# 1.net
KiCad netlist of a schematic drawn in EAGLE
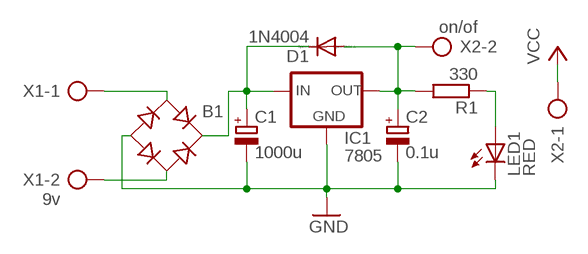
[diagram p0: schematic, sheet 1]
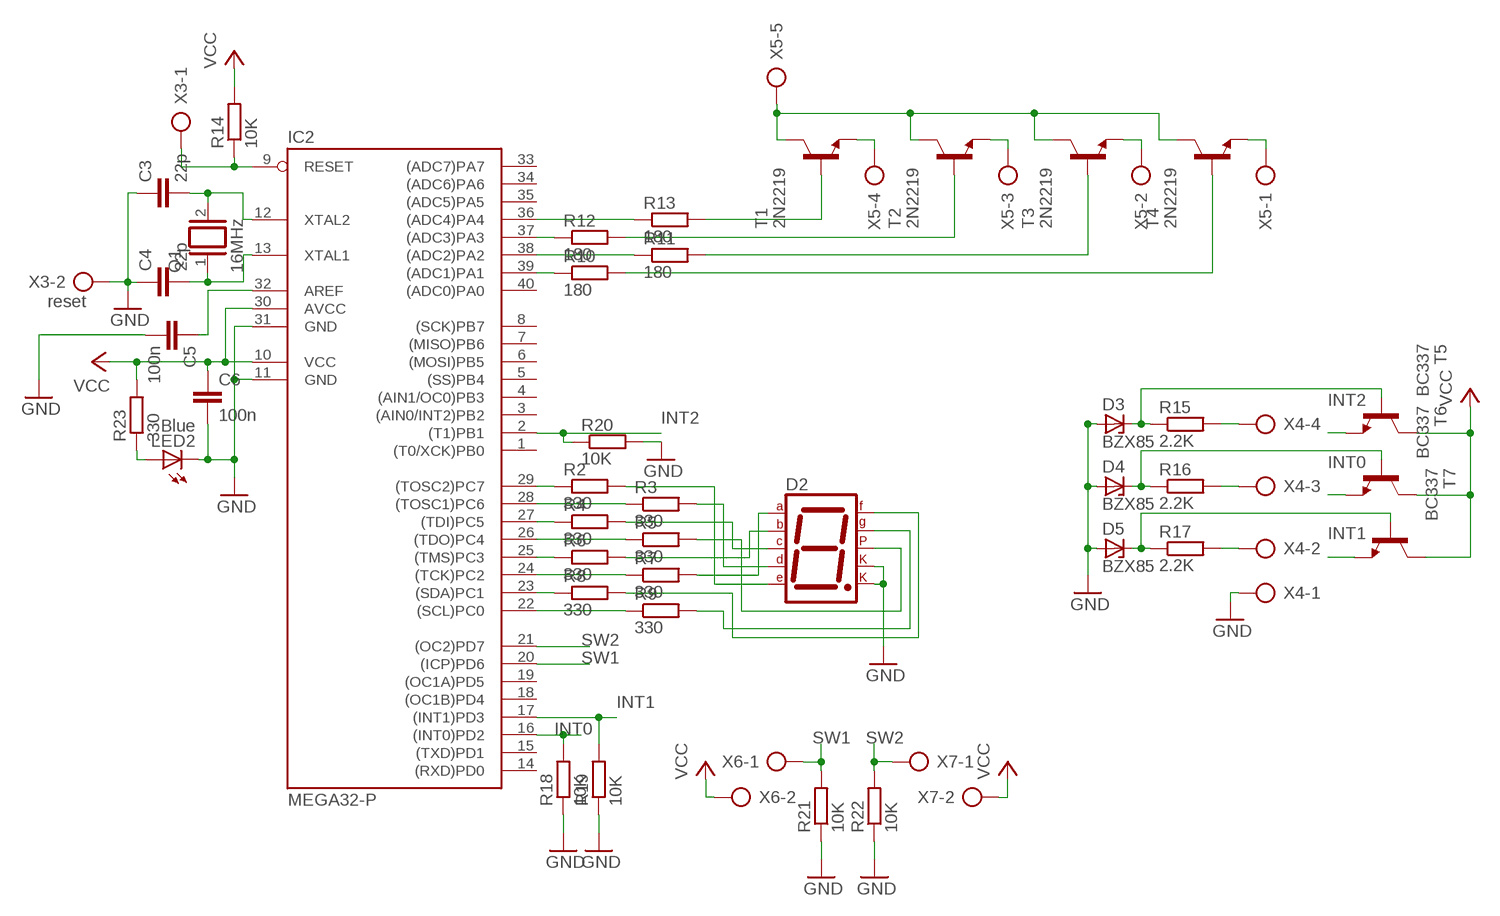
[diagram p1: schematic, sheet 2]

(export (version "E")
  (design (tool "Eeschema 10.0.6"))
  (components
    (comp (ref "B1")
      (value "RB1A")
      (footprint "eagle-import:RB1A")
      (libsource (lib "eagle-import") (part "RB1A"))
    )
    (comp (ref "C1")
      (value "1000u")
      (footprint "eagle-import:E3,5-8")
      (libsource (lib "eagle-import") (part "CPOL-EUE3.5-8"))
    )
    (comp (ref "C2")
      (value "0.1u")
      (footprint "eagle-import:E2-5")
      (libsource (lib "eagle-import") (part "CPOL-EUE2-5"))
    )
    (comp (ref "D1")
      (value "1N4004")
      (footprint "eagle-import:DO41-10")
      (libsource (lib "eagle-import") (part "1N4004"))
    )
    (comp (ref "IC1")
      (value "7805")
      (footprint "eagle-import:78XXS")
      (libsource (lib "eagle-import") (part "78XXS"))
    )
    (comp (ref "LED1")
      (value "RED")
      (footprint "eagle-import:LED5MM")
      (libsource (lib "eagle-import") (part "LED5MM"))
    )
    (comp (ref "R1")
      (value "330")
      (footprint "eagle-import:0204_7")
      (libsource (lib "eagle-import") (part "R-EU_0204/7"))
    )
    (comp (ref "X1")
      (value "9v")
      (footprint "eagle-import:AK500_2")
      (libsource (lib "eagle-import") (part "AK500/2"))
    )
    (comp (ref "X2")
      (value "on/of")
      (footprint "eagle-import:AK500_2")
      (libsource (lib "eagle-import") (part "AK500/2"))
    )
    (comp (ref "C3")
      (value "22p")
      (footprint "eagle-import:C025-024X044")
      (libsource (lib "eagle-import") (part "C-EU025-024X044"))
    )
    (comp (ref "C4")
      (value "22p")
      (footprint "eagle-import:C025-024X044")
      (libsource (lib "eagle-import") (part "C-EU025-024X044"))
    )
    (comp (ref "C5")
      (value "100n")
      (footprint "eagle-import:C025-024X044")
      (libsource (lib "eagle-import") (part "C-EU025-024X044"))
    )
    (comp (ref "C6")
      (value "100n")
      (footprint "eagle-import:C025-024X044")
      (libsource (lib "eagle-import") (part "C-EU025-024X044"))
    )
    (comp (ref "D2")
      (value "7SEG-CK")
      (footprint "eagle-import:7SEG-13")
      (libsource (lib "eagle-import") (part "7SEG-CK"))
    )
    (comp (ref "D3")
      (value "BZX85")
      (footprint "eagle-import:DO41Z10")
      (libsource (lib "eagle-import") (part "BZX85"))
    )
    (comp (ref "D4")
      (value "BZX85")
      (footprint "eagle-import:DO41Z10")
      (libsource (lib "eagle-import") (part "BZX85"))
    )
    (comp (ref "D5")
      (value "BZX85")
      (footprint "eagle-import:DO41Z10")
      (libsource (lib "eagle-import") (part "BZX85"))
    )
    (comp (ref "IC2")
      (value "MEGA32-P")
      (footprint "eagle-import:DIL40")
      (fields (field (name "MPN") "ATMEGA32-16PU"))
      (libsource (lib "eagle-import") (part "MEGA32-P"))
    )
    (comp (ref "LED2")
      (value "Blue")
      (footprint "eagle-import:LED5MM")
      (libsource (lib "eagle-import") (part "LED5MM"))
    )
    (comp (ref "Q1")
      (value "16MHz")
      (footprint "eagle-import:Q")
      (libsource (lib "eagle-import") (part "XTAL"))
    )
    (comp (ref "R2")
      (value "330")
      (footprint "eagle-import:0204_7")
      (libsource (lib "eagle-import") (part "R-EU_0204/7"))
    )
    (comp (ref "R3")
      (value "330")
      (footprint "eagle-import:0204_7")
      (libsource (lib "eagle-import") (part "R-EU_0204/7"))
    )
    (comp (ref "R4")
      (value "330")
      (footprint "eagle-import:0204_7")
      (libsource (lib "eagle-import") (part "R-EU_0204/7"))
    )
    (comp (ref "R5")
      (value "330")
      (footprint "eagle-import:0204_7")
      (libsource (lib "eagle-import") (part "R-EU_0204/7"))
    )
    (comp (ref "R6")
      (value "330")
      (footprint "eagle-import:0204_7")
      (libsource (lib "eagle-import") (part "R-EU_0204/7"))
    )
    (comp (ref "R7")
      (value "330")
      (footprint "eagle-import:0204_7")
      (libsource (lib "eagle-import") (part "R-EU_0204/7"))
    )
    (comp (ref "R8")
      (value "330")
      (footprint "eagle-import:0204_7")
      (libsource (lib "eagle-import") (part "R-EU_0204/7"))
    )
    (comp (ref "R9")
      (value "330")
      (footprint "eagle-import:0204_7")
      (libsource (lib "eagle-import") (part "R-EU_0204/7"))
    )
    (comp (ref "R10")
      (value "180")
      (footprint "eagle-import:0204_7")
      (libsource (lib "eagle-import") (part "R-EU_0204/7"))
    )
    (comp (ref "R11")
      (value "180")
      (footprint "eagle-import:0204_7")
      (libsource (lib "eagle-import") (part "R-EU_0204/7"))
    )
    (comp (ref "R12")
      (value "180")
      (footprint "eagle-import:0204_7")
      (libsource (lib "eagle-import") (part "R-EU_0204/7"))
    )
    (comp (ref "R13")
      (value "180")
      (footprint "eagle-import:0204_7")
      (libsource (lib "eagle-import") (part "R-EU_0204/7"))
    )
    (comp (ref "R14")
      (value "10K")
      (footprint "eagle-import:0204_7")
      (libsource (lib "eagle-import") (part "R-EU_0204/7"))
    )
    (comp (ref "R15")
      (value "2.2K")
      (footprint "eagle-import:0207_10")
      (libsource (lib "eagle-import") (part "R-EU_0207/10"))
    )
    (comp (ref "R16")
      (value "2.2K")
      (footprint "eagle-import:0207_10")
      (libsource (lib "eagle-import") (part "R-EU_0207/10"))
    )
    (comp (ref "R17")
      (value "2.2K")
      (footprint "eagle-import:0207_10")
      (libsource (lib "eagle-import") (part "R-EU_0207/10"))
    )
    (comp (ref "R18")
      (value "10K")
      (footprint "eagle-import:0204_7")
      (libsource (lib "eagle-import") (part "R-EU_0204/7"))
    )
    (comp (ref "R19")
      (value "10K")
      (footprint "eagle-import:0204_7")
      (libsource (lib "eagle-import") (part "R-EU_0204/7"))
    )
    (comp (ref "R20")
      (value "10K")
      (footprint "eagle-import:0204_7")
      (libsource (lib "eagle-import") (part "R-EU_0204/7"))
    )
    (comp (ref "R21")
      (value "10K")
      (footprint "eagle-import:0204_7")
      (libsource (lib "eagle-import") (part "R-EU_0204/7"))
    )
    (comp (ref "R22")
      (value "10K")
      (footprint "eagle-import:0204_7")
      (libsource (lib "eagle-import") (part "R-EU_0204/7"))
    )
    (comp (ref "R23")
      (value "330")
      (footprint "eagle-import:0204_7")
      (libsource (lib "eagle-import") (part "R-EU_0204/7"))
    )
    (comp (ref "T1")
      (value "2N2219")
      (footprint "eagle-import:TO5")
      (libsource (lib "eagle-import") (part "2N2219"))
    )
    (comp (ref "T2")
      (value "2N2219")
      (footprint "eagle-import:TO5")
      (libsource (lib "eagle-import") (part "2N2219"))
    )
    (comp (ref "T3")
      (value "2N2219")
      (footprint "eagle-import:TO5")
      (libsource (lib "eagle-import") (part "2N2219"))
    )
    (comp (ref "T4")
      (value "2N2219")
      (footprint "eagle-import:TO5")
      (libsource (lib "eagle-import") (part "2N2219"))
    )
    (comp (ref "T5")
      (value "BC337")
      (footprint "eagle-import:TO92")
      (libsource (lib "eagle-import") (part "BC337"))
    )
    (comp (ref "T6")
      (value "BC337")
      (footprint "eagle-import:TO92")
      (libsource (lib "eagle-import") (part "BC337"))
    )
    (comp (ref "T7")
      (value "BC337")
      (footprint "eagle-import:TO92")
      (libsource (lib "eagle-import") (part "BC337"))
    )
    (comp (ref "X3")
      (value "reset")
      (footprint "eagle-import:AK500_2")
      (libsource (lib "eagle-import") (part "AK500/2"))
    )
    (comp (ref "X4")
      (value "AK500/4")
      (footprint "eagle-import:AK500_4")
      (libsource (lib "eagle-import") (part "AK500/4"))
    )
    (comp (ref "X5")
      (value "AK500/5")
      (footprint "eagle-import:AK500_5")
      (libsource (lib "eagle-import") (part "AK500/5"))
    )
    (comp (ref "X6")
      (value "AK500/2")
      (footprint "eagle-import:AK500_2")
      (libsource (lib "eagle-import") (part "AK500/2"))
    )
    (comp (ref "X7")
      (value "AK500/2")
      (footprint "eagle-import:AK500_2")
      (libsource (lib "eagle-import") (part "AK500/2"))
    )
  )
  (nets
    (net (code "1") (name "GND") (class "Default")
      (node (ref "B1") (pin "-") (pinfunction "-_-") (pintype "passive"))
      (node (ref "C1") (pin "-") (pinfunction "-_-") (pintype "passive"))
      (node (ref "C2") (pin "-") (pinfunction "-_-") (pintype "passive"))
      (node (ref "C3") (pin "1") (pinfunction "1_1") (pintype "passive"))
      (node (ref "C4") (pin "1") (pinfunction "1_1") (pintype "passive"))
      (node (ref "C5") (pin "2") (pinfunction "2_2") (pintype "passive"))
      (node (ref "C6") (pin "2") (pinfunction "2_2") (pintype "passive"))
      (node (ref "D2") (pin "3") (pinfunction "CK1_3") (pintype "passive"))
      (node (ref "D2") (pin "8") (pinfunction "CK2_8") (pintype "passive"))
      (node (ref "D3") (pin "A") (pinfunction "A_A") (pintype "passive"))
      (node (ref "D4") (pin "A") (pinfunction "A_A") (pintype "passive"))
      (node (ref "D5") (pin "A") (pinfunction "A_A") (pintype "passive"))
      (node (ref "IC1") (pin "GND") (pinfunction "GND_GND") (pintype "input"))
      (node (ref "IC2") (pin "11") (pinfunction "GND_11") (pintype "power_in"))
      (node (ref "IC2") (pin "31") (pinfunction "GND_31") (pintype "power_in"))
      (node (ref "LED1") (pin "K") (pinfunction "C_K") (pintype "passive"))
      (node (ref "LED2") (pin "K") (pinfunction "C_K") (pintype "passive"))
      (node (ref "R18") (pin "1") (pinfunction "1_1") (pintype "passive"))
      (node (ref "R19") (pin "1") (pinfunction "1_1") (pintype "passive"))
      (node (ref "R20") (pin "2") (pinfunction "2_2") (pintype "passive"))
      (node (ref "R21") (pin "1") (pinfunction "1_1") (pintype "passive"))
      (node (ref "R22") (pin "1") (pinfunction "1_1") (pintype "passive"))
      (node (ref "X3") (pin "2") (pinfunction "KL_2") (pintype "passive"))
      (node (ref "X4") (pin "1") (pinfunction "KL_1") (pintype "passive"))
    )
    (net (code "2") (name "INT0") (class "Default")
      (node (ref "IC2") (pin "16") (pinfunction "(INT0)PD2_16") (pintype "bidirectional"))
      (node (ref "R18") (pin "2") (pinfunction "2_2") (pintype "passive"))
      (node (ref "T6") (pin "1") (pinfunction "E_1") (pintype "passive"))
    )
    (net (code "3") (name "INT1") (class "Default")
      (node (ref "IC2") (pin "17") (pinfunction "(INT1)PD3_17") (pintype "bidirectional"))
      (node (ref "R19") (pin "2") (pinfunction "2_2") (pintype "passive"))
      (node (ref "T7") (pin "1") (pinfunction "E_1") (pintype "passive"))
    )
    (net (code "4") (name "INT2") (class "Default")
      (node (ref "IC2") (pin "2") (pinfunction "(T1)PB1_2") (pintype "bidirectional"))
      (node (ref "R20") (pin "1") (pinfunction "1_1") (pintype "passive"))
      (node (ref "T5") (pin "1") (pinfunction "E_1") (pintype "passive"))
    )
    (net (code "5") (name "Net-(B1-Pad+)") (class "Default")
      (node (ref "B1") (pin "+") (pinfunction "+_+") (pintype "passive"))
      (node (ref "C1") (pin "+") (pinfunction "+_+") (pintype "passive"))
      (node (ref "D1") (pin "C") (pinfunction "C_C") (pintype "passive"))
      (node (ref "IC1") (pin "IN") (pinfunction "IN_IN") (pintype "input"))
    )
    (net (code "6") (name "Net-(D2-A)") (class "Default")
      (node (ref "D2") (pin "7") (pinfunction "A_7") (pintype "passive"))
      (node (ref "R7") (pin "2") (pinfunction "2_2") (pintype "passive"))
    )
    (net (code "7") (name "Net-(D2-B)") (class "Default")
      (node (ref "D2") (pin "6") (pinfunction "B_6") (pintype "passive"))
      (node (ref "R6") (pin "2") (pinfunction "2_2") (pintype "passive"))
    )
    (net (code "8") (name "Net-(D2-C)") (class "Default")
      (node (ref "D2") (pin "4") (pinfunction "C_4") (pintype "passive"))
      (node (ref "R4") (pin "2") (pinfunction "2_2") (pintype "passive"))
    )
    (net (code "9") (name "Net-(D2-D)") (class "Default")
      (node (ref "D2") (pin "2") (pinfunction "D_2") (pintype "passive"))
      (node (ref "R3") (pin "2") (pinfunction "2_2") (pintype "passive"))
    )
    (net (code "10") (name "Net-(D2-DP)") (class "Default")
      (node (ref "D2") (pin "5") (pinfunction "DP_5") (pintype "passive"))
      (node (ref "R5") (pin "2") (pinfunction "2_2") (pintype "passive"))
    )
    (net (code "11") (name "Net-(D2-E)") (class "Default")
      (node (ref "D2") (pin "1") (pinfunction "E_1") (pintype "passive"))
      (node (ref "R2") (pin "2") (pinfunction "2_2") (pintype "passive"))
    )
    (net (code "12") (name "Net-(D2-F)") (class "Default")
      (node (ref "D2") (pin "9") (pinfunction "F_9") (pintype "passive"))
      (node (ref "R8") (pin "2") (pinfunction "2_2") (pintype "passive"))
    )
    (net (code "13") (name "Net-(D2-G)") (class "Default")
      (node (ref "D2") (pin "10") (pinfunction "G_10") (pintype "passive"))
      (node (ref "R9") (pin "2") (pinfunction "2_2") (pintype "passive"))
    )
    (net (code "14") (name "Net-(IC2-(ADC1)PA1)") (class "Default")
      (node (ref "IC2") (pin "39") (pinfunction "(ADC1)PA1_39") (pintype "bidirectional"))
      (node (ref "R10") (pin "1") (pinfunction "1_1") (pintype "passive"))
    )
    (net (code "15") (name "Net-(IC2-(ADC2)PA2)") (class "Default")
      (node (ref "IC2") (pin "38") (pinfunction "(ADC2)PA2_38") (pintype "bidirectional"))
      (node (ref "R11") (pin "1") (pinfunction "1_1") (pintype "passive"))
    )
    (net (code "16") (name "Net-(IC2-(ADC3)PA3)") (class "Default")
      (node (ref "IC2") (pin "37") (pinfunction "(ADC3)PA3_37") (pintype "bidirectional"))
      (node (ref "R12") (pin "1") (pinfunction "1_1") (pintype "passive"))
    )
    (net (code "17") (name "Net-(IC2-(ADC4)PA4)") (class "Default")
      (node (ref "IC2") (pin "36") (pinfunction "(ADC4)PA4_36") (pintype "bidirectional"))
      (node (ref "R13") (pin "1") (pinfunction "1_1") (pintype "passive"))
    )
    (net (code "18") (name "Net-(IC2-(SCL)PC0)") (class "Default")
      (node (ref "IC2") (pin "22") (pinfunction "(SCL)PC0_22") (pintype "bidirectional"))
      (node (ref "R9") (pin "1") (pinfunction "1_1") (pintype "passive"))
    )
    (net (code "19") (name "Net-(IC2-(SDA)PC1)") (class "Default")
      (node (ref "IC2") (pin "23") (pinfunction "(SDA)PC1_23") (pintype "bidirectional"))
      (node (ref "R8") (pin "1") (pinfunction "1_1") (pintype "passive"))
    )
    (net (code "20") (name "Net-(IC2-(TCK)PC2)") (class "Default")
      (node (ref "IC2") (pin "24") (pinfunction "(TCK)PC2_24") (pintype "bidirectional"))
      (node (ref "R7") (pin "1") (pinfunction "1_1") (pintype "passive"))
    )
    (net (code "21") (name "Net-(IC2-(TDI)PC5)") (class "Default")
      (node (ref "IC2") (pin "27") (pinfunction "(TDI)PC5_27") (pintype "bidirectional"))
      (node (ref "R4") (pin "1") (pinfunction "1_1") (pintype "passive"))
    )
    (net (code "22") (name "Net-(IC2-(TDO)PC4)") (class "Default")
      (node (ref "IC2") (pin "26") (pinfunction "(TDO)PC4_26") (pintype "bidirectional"))
      (node (ref "R5") (pin "1") (pinfunction "1_1") (pintype "passive"))
    )
    (net (code "23") (name "Net-(IC2-(TMS)PC3)") (class "Default")
      (node (ref "IC2") (pin "25") (pinfunction "(TMS)PC3_25") (pintype "bidirectional"))
      (node (ref "R6") (pin "1") (pinfunction "1_1") (pintype "passive"))
    )
    (net (code "24") (name "Net-(IC2-(TOSC1)PC6)") (class "Default")
      (node (ref "IC2") (pin "28") (pinfunction "(TOSC1)PC6_28") (pintype "bidirectional"))
      (node (ref "R3") (pin "1") (pinfunction "1_1") (pintype "passive"))
    )
    (net (code "25") (name "Net-(IC2-(TOSC2)PC7)") (class "Default")
      (node (ref "IC2") (pin "29") (pinfunction "(TOSC2)PC7_29") (pintype "bidirectional"))
      (node (ref "R2") (pin "1") (pinfunction "1_1") (pintype "passive"))
    )
    (net (code "26") (name "Net-(IC2-AREF)") (class "Default")
      (node (ref "C5") (pin "1") (pinfunction "1_1") (pintype "passive"))
      (node (ref "IC2") (pin "32") (pinfunction "AREF_32") (pintype "passive"))
    )
    (net (code "27") (name "Net-(IC2-RESET)") (class "Default")
      (node (ref "IC2") (pin "9") (pinfunction "RESET_9") (pintype "input"))
      (node (ref "R14") (pin "1") (pinfunction "1_1") (pintype "passive"))
      (node (ref "X3") (pin "1") (pinfunction "KL_1") (pintype "passive"))
    )
    (net (code "28") (name "Net-(IC2-XTAL1)") (class "Default")
      (node (ref "C4") (pin "2") (pinfunction "2_2") (pintype "passive"))
      (node (ref "IC2") (pin "13") (pinfunction "XTAL1_13") (pintype "bidirectional"))
      (node (ref "Q1") (pin "1") (pinfunction "1_1") (pintype "passive"))
    )
    (net (code "29") (name "Net-(IC2-XTAL2)") (class "Default")
      (node (ref "C3") (pin "2") (pinfunction "2_2") (pintype "passive"))
      (node (ref "IC2") (pin "12") (pinfunction "XTAL2_12") (pintype "bidirectional"))
      (node (ref "Q1") (pin "2") (pinfunction "2_2") (pintype "passive"))
    )
    (net (code "30") (name "Net-(LED1-PadA)") (class "Default")
      (node (ref "LED1") (pin "A") (pinfunction "A_A") (pintype "passive"))
      (node (ref "R1") (pin "1") (pinfunction "1_1") (pintype "passive"))
    )
    (net (code "31") (name "Net-(LED2-PadA)") (class "Default")
      (node (ref "LED2") (pin "A") (pinfunction "A_A") (pintype "passive"))
      (node (ref "R23") (pin "1") (pinfunction "1_1") (pintype "passive"))
    )
    (net (code "32") (name "Net-(T1-B)") (class "Default")
      (node (ref "R13") (pin "2") (pinfunction "2_2") (pintype "passive"))
      (node (ref "T1") (pin "2") (pinfunction "B_2") (pintype "passive"))
    )
    (net (code "33") (name "Net-(T1-C)") (class "Default")
      (node (ref "T1") (pin "3") (pinfunction "C_3") (pintype "passive"))
      (node (ref "T2") (pin "3") (pinfunction "C_3") (pintype "passive"))
      (node (ref "T3") (pin "3") (pinfunction "C_3") (pintype "passive"))
      (node (ref "T4") (pin "3") (pinfunction "C_3") (pintype "passive"))
      (node (ref "X5") (pin "5") (pinfunction "KL_5") (pintype "passive"))
    )
    (net (code "34") (name "Net-(T1-E)") (class "Default")
      (node (ref "T1") (pin "1") (pinfunction "E_1") (pintype "passive"))
      (node (ref "X5") (pin "4") (pinfunction "KL_4") (pintype "passive"))
    )
    (net (code "35") (name "Net-(T2-B)") (class "Default")
      (node (ref "R12") (pin "2") (pinfunction "2_2") (pintype "passive"))
      (node (ref "T2") (pin "2") (pinfunction "B_2") (pintype "passive"))
    )
    (net (code "36") (name "Net-(T2-E)") (class "Default")
      (node (ref "T2") (pin "1") (pinfunction "E_1") (pintype "passive"))
      (node (ref "X5") (pin "3") (pinfunction "KL_3") (pintype "passive"))
    )
    (net (code "37") (name "Net-(T3-B)") (class "Default")
      (node (ref "R11") (pin "2") (pinfunction "2_2") (pintype "passive"))
      (node (ref "T3") (pin "2") (pinfunction "B_2") (pintype "passive"))
    )
    (net (code "38") (name "Net-(T3-E)") (class "Default")
      (node (ref "T3") (pin "1") (pinfunction "E_1") (pintype "passive"))
      (node (ref "X5") (pin "2") (pinfunction "KL_2") (pintype "passive"))
    )
    (net (code "39") (name "Net-(T4-B)") (class "Default")
      (node (ref "R10") (pin "2") (pinfunction "2_2") (pintype "passive"))
      (node (ref "T4") (pin "2") (pinfunction "B_2") (pintype "passive"))
    )
    (net (code "40") (name "Net-(T4-E)") (class "Default")
      (node (ref "T4") (pin "1") (pinfunction "E_1") (pintype "passive"))
      (node (ref "X5") (pin "1") (pinfunction "KL_1") (pintype "passive"))
    )
    (net (code "41") (name "Net-(T5-B)") (class "Default")
      (node (ref "D3") (pin "C") (pinfunction "C_C") (pintype "passive"))
      (node (ref "R15") (pin "1") (pinfunction "1_1") (pintype "passive"))
      (node (ref "T5") (pin "2") (pinfunction "B_2") (pintype "passive"))
    )
    (net (code "42") (name "Net-(T6-B)") (class "Default")
      (node (ref "D4") (pin "C") (pinfunction "C_C") (pintype "passive"))
      (node (ref "R16") (pin "1") (pinfunction "1_1") (pintype "passive"))
      (node (ref "T6") (pin "2") (pinfunction "B_2") (pintype "passive"))
    )
    (net (code "43") (name "Net-(T7-B)") (class "Default")
      (node (ref "D5") (pin "C") (pinfunction "C_C") (pintype "passive"))
      (node (ref "R17") (pin "1") (pinfunction "1_1") (pintype "passive"))
      (node (ref "T7") (pin "2") (pinfunction "B_2") (pintype "passive"))
    )
    (net (code "44") (name "Net-(X1A-KL)") (class "Default")
      (node (ref "B1") (pin "AC1") (pinfunction "AC1_AC1") (pintype "passive"))
      (node (ref "X1") (pin "1") (pinfunction "KL_1") (pintype "passive"))
    )
    (net (code "45") (name "Net-(X1B-KL)") (class "Default")
      (node (ref "B1") (pin "AC2") (pinfunction "AC2_AC2") (pintype "passive"))
      (node (ref "X1") (pin "2") (pinfunction "KL_2") (pintype "passive"))
    )
    (net (code "46") (name "Net-(X2B-KL)") (class "Default")
      (node (ref "C2") (pin "+") (pinfunction "+_+") (pintype "passive"))
      (node (ref "D1") (pin "A") (pinfunction "A_A") (pintype "passive"))
      (node (ref "IC1") (pin "OUT") (pinfunction "OUT_OUT") (pintype "passive"))
      (node (ref "R1") (pin "2") (pinfunction "2_2") (pintype "passive"))
      (node (ref "X2") (pin "2") (pinfunction "KL_2") (pintype "passive"))
    )
    (net (code "47") (name "Net-(X4B-KL)") (class "Default")
      (node (ref "R17") (pin "2") (pinfunction "2_2") (pintype "passive"))
      (node (ref "X4") (pin "2") (pinfunction "KL_2") (pintype "passive"))
    )
    (net (code "48") (name "Net-(X4C-KL)") (class "Default")
      (node (ref "R16") (pin "2") (pinfunction "2_2") (pintype "passive"))
      (node (ref "X4") (pin "3") (pinfunction "KL_3") (pintype "passive"))
    )
    (net (code "49") (name "Net-(X4D-KL)") (class "Default")
      (node (ref "R15") (pin "2") (pinfunction "2_2") (pintype "passive"))
      (node (ref "X4") (pin "4") (pinfunction "KL_4") (pintype "passive"))
    )
    (net (code "50") (name "SW1") (class "Default")
      (node (ref "IC2") (pin "20") (pinfunction "(ICP)PD6_20") (pintype "bidirectional"))
      (node (ref "R21") (pin "2") (pinfunction "2_2") (pintype "passive"))
      (node (ref "X6") (pin "1") (pinfunction "KL_1") (pintype "passive"))
    )
    (net (code "51") (name "SW2") (class "Default")
      (node (ref "IC2") (pin "21") (pinfunction "(OC2)PD7_21") (pintype "bidirectional"))
      (node (ref "R22") (pin "2") (pinfunction "2_2") (pintype "passive"))
      (node (ref "X7") (pin "1") (pinfunction "KL_1") (pintype "passive"))
    )
    (net (code "52") (name "VCC") (class "Default")
      (node (ref "C6") (pin "1") (pinfunction "1_1") (pintype "passive"))
      (node (ref "IC2") (pin "10") (pinfunction "VCC_10") (pintype "power_in"))
      (node (ref "IC2") (pin "30") (pinfunction "AVCC_30") (pintype "power_in"))
      (node (ref "R14") (pin "2") (pinfunction "2_2") (pintype "passive"))
      (node (ref "R23") (pin "2") (pinfunction "2_2") (pintype "passive"))
      (node (ref "T5") (pin "3") (pinfunction "C_3") (pintype "passive"))
      (node (ref "T6") (pin "3") (pinfunction "C_3") (pintype "passive"))
      (node (ref "T7") (pin "3") (pinfunction "C_3") (pintype "passive"))
      (node (ref "X2") (pin "1") (pinfunction "KL_1") (pintype "passive"))
      (node (ref "X6") (pin "2") (pinfunction "KL_2") (pintype "passive"))
      (node (ref "X7") (pin "2") (pinfunction "KL_2") (pintype "passive"))
    )
    (net (code "53") (name "unconnected-(IC2-(ADC0)PA0-Pad40)") (class "Default")
      (node (ref "IC2") (pin "40") (pinfunction "(ADC0)PA0_40") (pintype "bidirectional"))
    )
    (net (code "54") (name "unconnected-(IC2-(ADC5)PA5-Pad35)") (class "Default")
      (node (ref "IC2") (pin "35") (pinfunction "(ADC5)PA5_35") (pintype "bidirectional"))
    )
    (net (code "55") (name "unconnected-(IC2-(ADC6)PA6-Pad34)") (class "Default")
      (node (ref "IC2") (pin "34") (pinfunction "(ADC6)PA6_34") (pintype "bidirectional"))
    )
    (net (code "56") (name "unconnected-(IC2-(ADC7)PA7-Pad33)") (class "Default")
      (node (ref "IC2") (pin "33") (pinfunction "(ADC7)PA7_33") (pintype "bidirectional"))
    )
    (net (code "57") (name "unconnected-(IC2-(AIN0{slash}INT2)PB2-Pad3)") (class "Default")
      (node (ref "IC2") (pin "3") (pinfunction "(AIN0/INT2)PB2_3") (pintype "bidirectional"))
    )
    (net (code "58") (name "unconnected-(IC2-(AIN1{slash}OC0)PB3-Pad4)") (class "Default")
      (node (ref "IC2") (pin "4") (pinfunction "(AIN1/OC0)PB3_4") (pintype "bidirectional"))
    )
    (net (code "59") (name "unconnected-(IC2-(MISO)PB6-Pad7)") (class "Default")
      (node (ref "IC2") (pin "7") (pinfunction "(MISO)PB6_7") (pintype "bidirectional"))
    )
    (net (code "60") (name "unconnected-(IC2-(MOSI)PB5-Pad6)") (class "Default")
      (node (ref "IC2") (pin "6") (pinfunction "(MOSI)PB5_6") (pintype "bidirectional"))
    )
    (net (code "61") (name "unconnected-(IC2-(OC1A)PD5-Pad19)") (class "Default")
      (node (ref "IC2") (pin "19") (pinfunction "(OC1A)PD5_19") (pintype "bidirectional"))
    )
    (net (code "62") (name "unconnected-(IC2-(OC1B)PD4-Pad18)") (class "Default")
      (node (ref "IC2") (pin "18") (pinfunction "(OC1B)PD4_18") (pintype "bidirectional"))
    )
    (net (code "63") (name "unconnected-(IC2-(RXD)PD0-Pad14)") (class "Default")
      (node (ref "IC2") (pin "14") (pinfunction "(RXD)PD0_14") (pintype "bidirectional"))
    )
    (net (code "64") (name "unconnected-(IC2-(SCK)PB7-Pad8)") (class "Default")
      (node (ref "IC2") (pin "8") (pinfunction "(SCK)PB7_8") (pintype "bidirectional"))
    )
    (net (code "65") (name "unconnected-(IC2-(SS)PB4-Pad5)") (class "Default")
      (node (ref "IC2") (pin "5") (pinfunction "(SS)PB4_5") (pintype "bidirectional"))
    )
    (net (code "66") (name "unconnected-(IC2-(T0{slash}XCK)PB0-Pad1)") (class "Default")
      (node (ref "IC2") (pin "1") (pinfunction "(T0/XCK)PB0_1") (pintype "bidirectional"))
    )
    (net (code "67") (name "unconnected-(IC2-(TXD)PD1-Pad15)") (class "Default")
      (node (ref "IC2") (pin "15") (pinfunction "(TXD)PD1_15") (pintype "bidirectional"))
    )
  )
)
